# b2b.net
KiCad netlist of a schematic drawn in Altium Designer
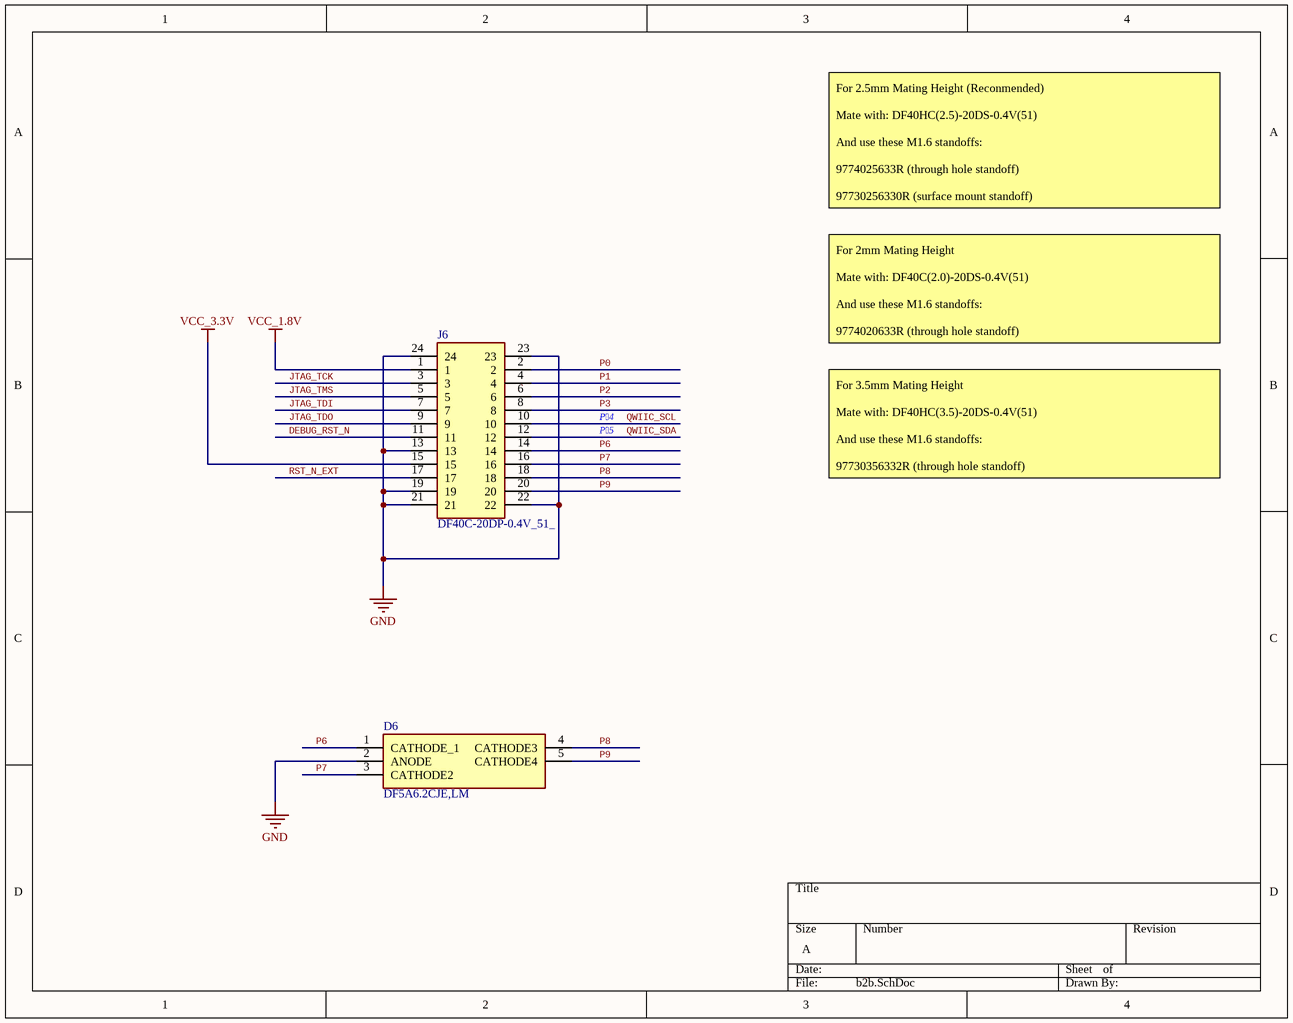
[diagram p0: b2b.SchDoc]

(export (version "E")
  (design (tool "Eeschema 10.0.6"))
  (components
    (comp (ref "D6")
      (value "DF5A6.2CJE,LM")
      (footprint "SamacSys:SOTFL50P160X60-5N")
      (description "Diode")
      (fields (field (name "MOUSER PART NUMBER") "757-DF5A6.2CJE,LM"))
      (libsource (lib "openmv-ae3") (part "DF5A5.6CJE,LM"))
    )
    (comp (ref "J6")
      (value "DF40C-20DP-0.4V_51_")
      (footprint "SamacSys:DF40C20DP04V51")
      (description "Connector")
      (fields
        (field (name "MANUFACTURER_PART_NUMBER") "DF40C-20DP-0.4V(51)")
        (field (name "MOUSER PART NUMBER") "798-DF40C20DP0.4V51")
      )
      (libsource (lib "*") (part "DF40C-20DP-0.4V_51_"))
    )
  )
  (nets
    (net (code "1") (name "/DEBUG_RST_N") (class "Default")
      (node (ref "J6") (pin "11") (pinfunction "11_11") (pintype "passive"))
    )
    (net (code "2") (name "/JTAG_TCK") (class "Default")
      (node (ref "J6") (pin "3") (pinfunction "3_3") (pintype "passive"))
    )
    (net (code "3") (name "/JTAG_TDI") (class "Default")
      (node (ref "J6") (pin "7") (pinfunction "7_7") (pintype "passive"))
    )
    (net (code "4") (name "/JTAG_TDO") (class "Default")
      (node (ref "J6") (pin "9") (pinfunction "9_9") (pintype "passive"))
    )
    (net (code "5") (name "/JTAG_TMS") (class "Default")
      (node (ref "J6") (pin "5") (pinfunction "5_5") (pintype "passive"))
    )
    (net (code "6") (name "/P0") (class "Default")
      (node (ref "J6") (pin "2") (pinfunction "2_2") (pintype "passive"))
    )
    (net (code "7") (name "/P1") (class "Default")
      (node (ref "J6") (pin "4") (pinfunction "4_4") (pintype "passive"))
    )
    (net (code "8") (name "/P2") (class "Default")
      (node (ref "J6") (pin "6") (pinfunction "6_6") (pintype "passive"))
    )
    (net (code "9") (name "/P3") (class "Default")
      (node (ref "J6") (pin "8") (pinfunction "8_8") (pintype "passive"))
    )
    (net (code "10") (name "/P6") (class "Default")
      (node (ref "D6") (pin "1") (pinfunction "CATHODE_1_1") (pintype "passive"))
      (node (ref "J6") (pin "14") (pinfunction "14_14") (pintype "passive"))
    )
    (net (code "11") (name "/P7") (class "Default")
      (node (ref "D6") (pin "3") (pinfunction "CATHODE2_3") (pintype "passive"))
      (node (ref "J6") (pin "16") (pinfunction "16_16") (pintype "passive"))
    )
    (net (code "12") (name "/P8") (class "Default")
      (node (ref "D6") (pin "4") (pinfunction "CATHODE3_4") (pintype "passive"))
      (node (ref "J6") (pin "18") (pinfunction "18_18") (pintype "passive"))
    )
    (net (code "13") (name "/P9") (class "Default")
      (node (ref "D6") (pin "5") (pinfunction "CATHODE4_5") (pintype "passive"))
      (node (ref "J6") (pin "20") (pinfunction "20_20") (pintype "passive"))
    )
    (net (code "14") (name "/QWIIC_SCL") (class "Default")
      (node (ref "J6") (pin "10") (pinfunction "10_10") (pintype "passive"))
    )
    (net (code "15") (name "/QWIIC_SDA") (class "Default")
      (node (ref "J6") (pin "12") (pinfunction "12_12") (pintype "passive"))
    )
    (net (code "16") (name "/RST_N_EXT") (class "Default")
      (node (ref "J6") (pin "17") (pinfunction "17_17") (pintype "passive"))
    )
    (net (code "17") (name "GND") (class "Default")
      (node (ref "D6") (pin "2") (pinfunction "ANODE_2") (pintype "passive"))
      (node (ref "J6") (pin "13") (pinfunction "13_13") (pintype "passive"))
      (node (ref "J6") (pin "19") (pinfunction "19_19") (pintype "passive"))
      (node (ref "J6") (pin "21") (pinfunction "21_21") (pintype "passive"))
      (node (ref "J6") (pin "22") (pinfunction "22_22") (pintype "passive"))
      (node (ref "J6") (pin "23") (pinfunction "23_23") (pintype "passive"))
      (node (ref "J6") (pin "24") (pinfunction "24_24") (pintype "passive"))
    )
    (net (code "18") (name "VCC_1.8V") (class "Default")
      (node (ref "J6") (pin "1") (pinfunction "1_1") (pintype "passive"))
    )
    (net (code "19") (name "VCC_3.3V") (class "Default")
      (node (ref "J6") (pin "15") (pinfunction "15_15") (pintype "passive"))
    )
  )
)
